# tennisfortwoL151.net
KiCad netlist of a schematic drawn in EAGLE
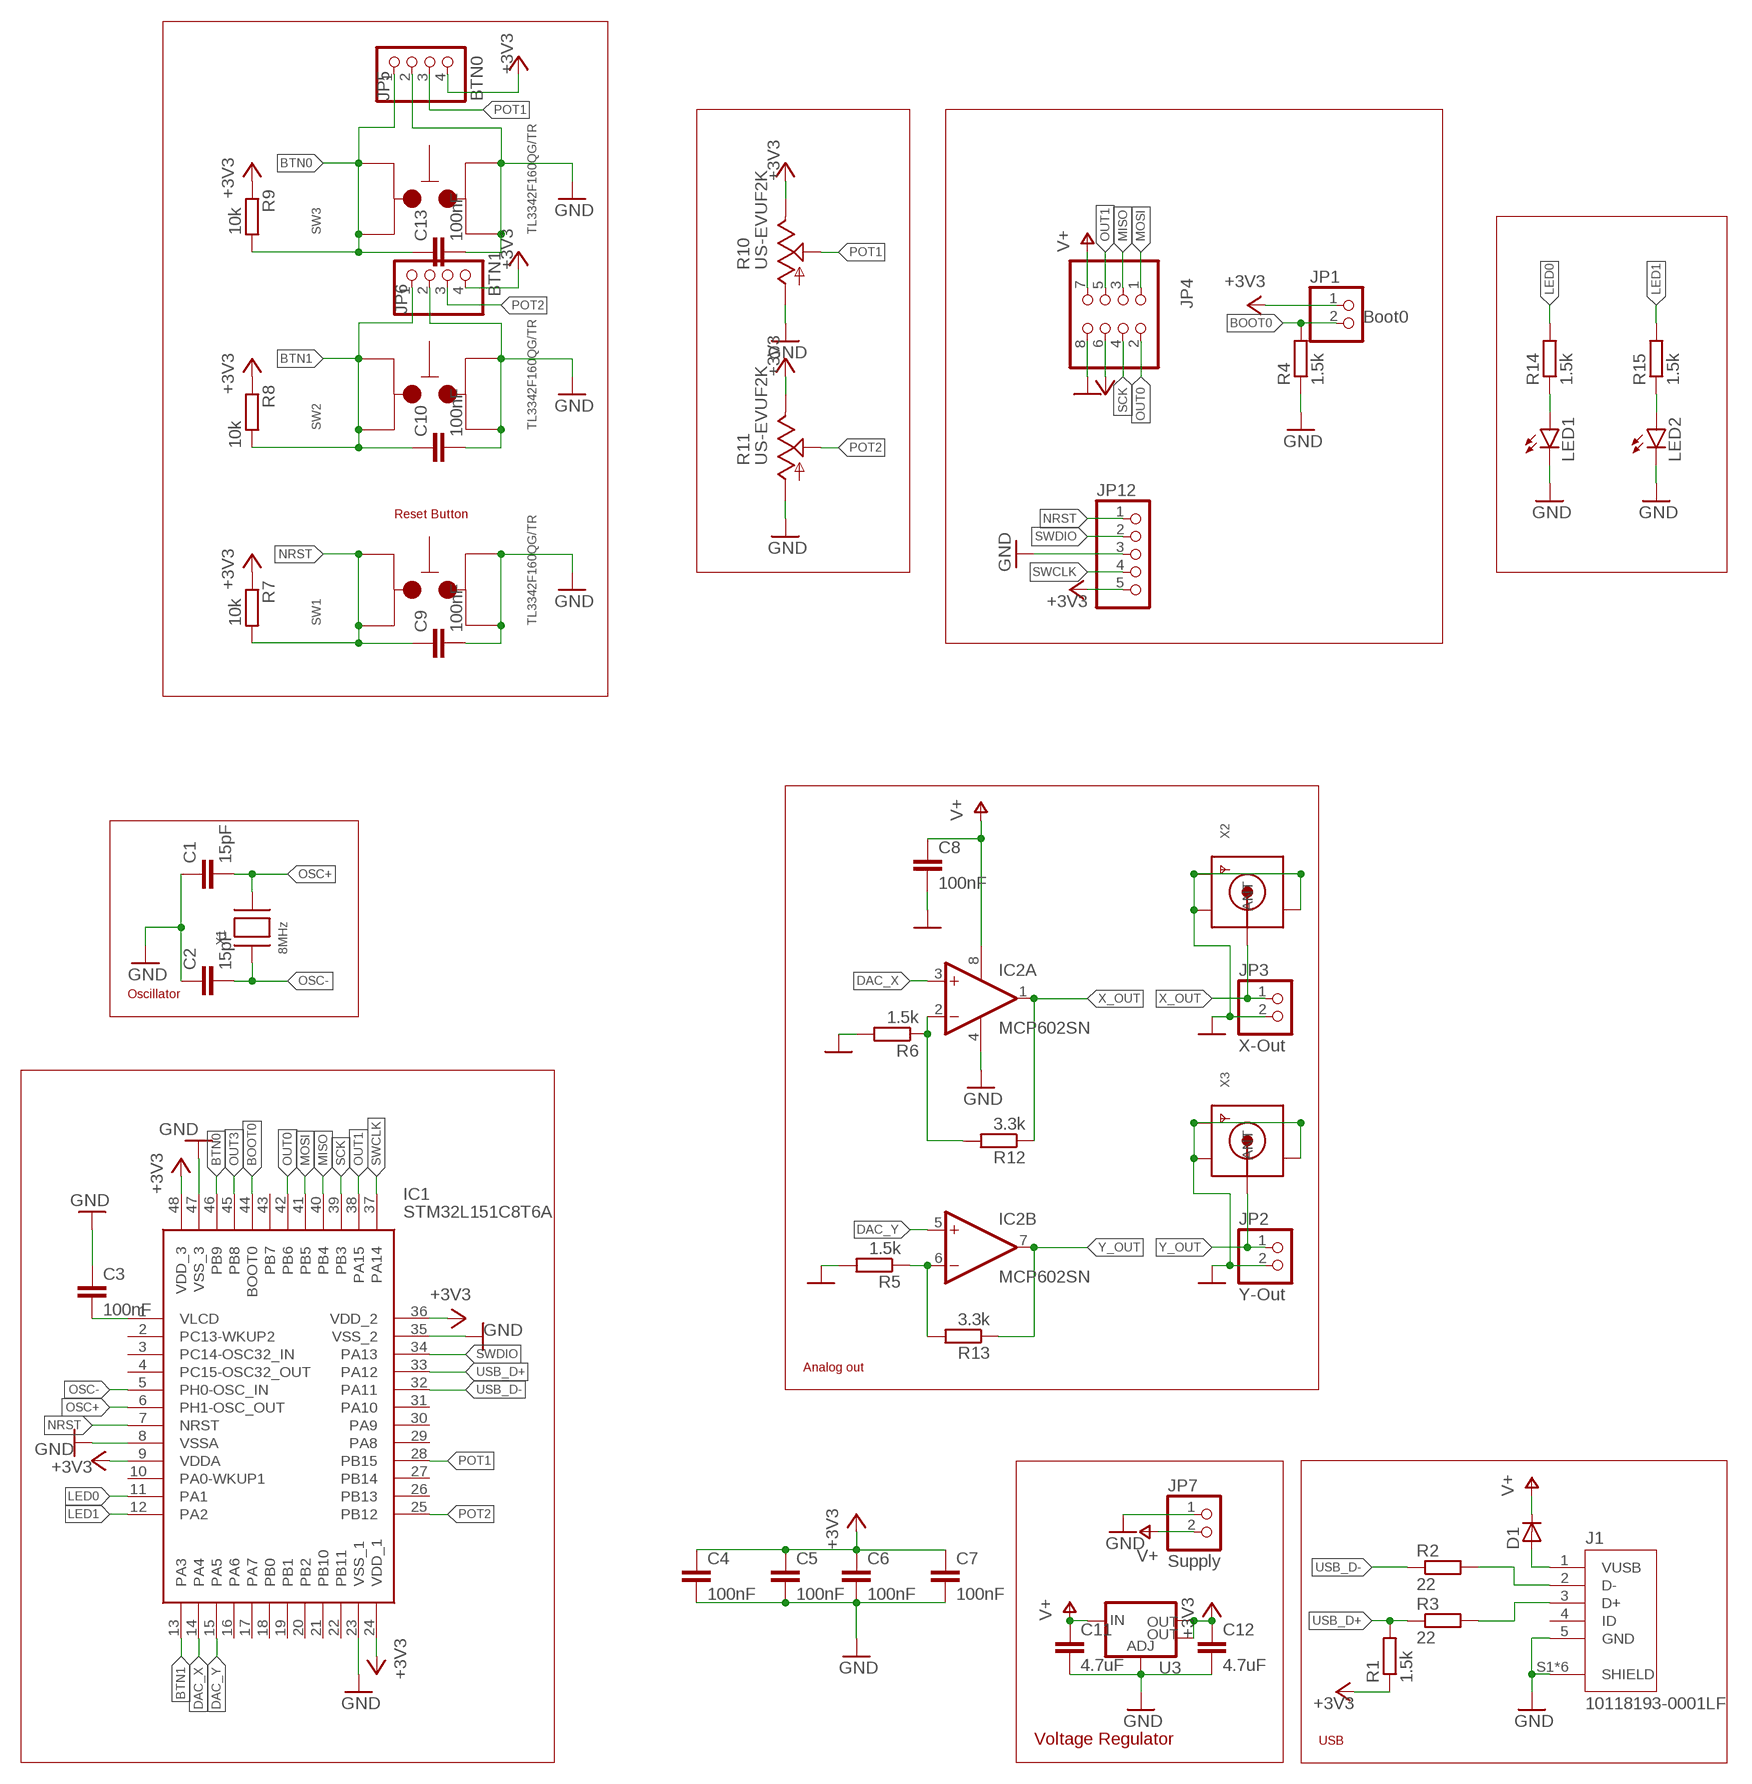
[diagram p0: schematic, sheet 1]

(export (version "E")
  (design (tool "Eeschema 10.0.6"))
  (components
    (comp (ref "C1")
      (value "15pF")
      (footprint "eagle-import:C0603")
      (libsource (lib "eagle-import") (part "C-EUC0603"))
    )
    (comp (ref "C2")
      (value "15pF")
      (footprint "eagle-import:C0603")
      (libsource (lib "eagle-import") (part "C-EUC0603"))
    )
    (comp (ref "C3")
      (value "100nF")
      (footprint "eagle-import:C0603")
      (libsource (lib "eagle-import") (part "C-EUC0603"))
    )
    (comp (ref "C4")
      (value "100nF")
      (footprint "eagle-import:C0603")
      (libsource (lib "eagle-import") (part "C-EUC0603"))
    )
    (comp (ref "C5")
      (value "100nF")
      (footprint "eagle-import:C0603")
      (libsource (lib "eagle-import") (part "C-EUC0603"))
    )
    (comp (ref "C6")
      (value "100nF")
      (footprint "eagle-import:C0603")
      (libsource (lib "eagle-import") (part "C-EUC0603"))
    )
    (comp (ref "C7")
      (value "100nF")
      (footprint "eagle-import:C0603")
      (libsource (lib "eagle-import") (part "C-EUC0603"))
    )
    (comp (ref "C8")
      (value "100nF")
      (footprint "eagle-import:C0603")
      (libsource (lib "eagle-import") (part "C-EUC0603"))
    )
    (comp (ref "C9")
      (value "100nF")
      (footprint "eagle-import:C0603")
      (libsource (lib "eagle-import") (part "C-EUC0603"))
    )
    (comp (ref "C10")
      (value "100nF")
      (footprint "eagle-import:C0603")
      (libsource (lib "eagle-import") (part "C-EUC0603"))
    )
    (comp (ref "C11")
      (value "4.7uF")
      (footprint "eagle-import:C0805")
      (libsource (lib "eagle-import") (part "C-EUC0805"))
    )
    (comp (ref "C12")
      (value "4.7uF")
      (footprint "eagle-import:C0805")
      (libsource (lib "eagle-import") (part "C-EUC0805"))
    )
    (comp (ref "C13")
      (value "100nF")
      (footprint "eagle-import:C0603")
      (libsource (lib "eagle-import") (part "C-EUC0603"))
    )
    (comp (ref "D1")
      (value "DIODESMA")
      (footprint "eagle-import:SMADIODE")
      (libsource (lib "eagle-import") (part "DIODESMA"))
    )
    (comp (ref "IC1")
      (value "STM32L151C8T6A")
      (footprint "eagle-import:QFP50P900X900X160-48N")
      (fields (field (name "MOUSER_PART_NUMBER") "511-STM32L151C8T6A"))
      (libsource (lib "eagle-import") (part "STM32L151C8T6A"))
    )
    (comp (ref "IC2")
      (value "MCP602SN")
      (footprint "eagle-import:SO08")
      (libsource (lib "eagle-import") (part "MCP602SN"))
    )
    (comp (ref "J1")
      (value "10118193-0001LF")
      (footprint "eagle-import:FCI_10118193-0001LF")
      (fields (field (name "MF") "Amphenol ICC"))
      (libsource (lib "eagle-import") (part "10118193-0001LF"))
    )
    (comp (ref "JP1")
      (value "Boot0")
      (footprint "eagle-import:1X02")
      (libsource (lib "eagle-import") (part "PINHD-1X2"))
    )
    (comp (ref "JP2")
      (value "Y-Out")
      (footprint "eagle-import:1X02")
      (libsource (lib "eagle-import") (part "PINHD-1X2"))
    )
    (comp (ref "JP3")
      (value "X-Out")
      (footprint "eagle-import:1X02")
      (libsource (lib "eagle-import") (part "PINHD-1X2"))
    )
    (comp (ref "JP4")
      (value "PINHD-2X4")
      (footprint "eagle-import:2X04")
      (libsource (lib "eagle-import") (part "PINHD-2X4"))
    )
    (comp (ref "JP5")
      (value "BTN0")
      (footprint "eagle-import:1X04_90")
      (libsource (lib "eagle-import") (part "PINHD-1X4/90"))
    )
    (comp (ref "JP6")
      (value "BTN1")
      (footprint "eagle-import:1X04_90")
      (libsource (lib "eagle-import") (part "PINHD-1X4/90"))
    )
    (comp (ref "JP7")
      (value "Supply")
      (footprint "eagle-import:1X02")
      (libsource (lib "eagle-import") (part "PINHD-1X2"))
    )
    (comp (ref "JP12")
      (value "PINHD-1X5")
      (footprint "eagle-import:1X05")
      (libsource (lib "eagle-import") (part "PINHD-1X5"))
    )
    (comp (ref "LED1")
      (value "LEDCHIPLED_0805")
      (footprint "eagle-import:CHIPLED_0805")
      (libsource (lib "eagle-import") (part "LEDCHIPLED_0805"))
    )
    (comp (ref "LED2")
      (value "LEDCHIPLED_0805")
      (footprint "eagle-import:CHIPLED_0805")
      (libsource (lib "eagle-import") (part "LEDCHIPLED_0805"))
    )
    (comp (ref "R1")
      (value "1.5k")
      (footprint "eagle-import:R0603")
      (libsource (lib "eagle-import") (part "R-EU_R0603"))
    )
    (comp (ref "R2")
      (value "22")
      (footprint "eagle-import:R0603")
      (libsource (lib "eagle-import") (part "R-EU_R0603"))
    )
    (comp (ref "R3")
      (value "22")
      (footprint "eagle-import:R0603")
      (libsource (lib "eagle-import") (part "R-EU_R0603"))
    )
    (comp (ref "R4")
      (value "1.5k")
      (footprint "eagle-import:R0603")
      (libsource (lib "eagle-import") (part "R-EU_R0603"))
    )
    (comp (ref "R5")
      (value "1.5k")
      (footprint "eagle-import:R0603")
      (libsource (lib "eagle-import") (part "R-EU_R0603"))
    )
    (comp (ref "R6")
      (value "1.5k")
      (footprint "eagle-import:R0603")
      (libsource (lib "eagle-import") (part "R-EU_R0603"))
    )
    (comp (ref "R7")
      (value "10k")
      (footprint "eagle-import:R0603")
      (libsource (lib "eagle-import") (part "R-EU_R0603"))
    )
    (comp (ref "R8")
      (value "10k")
      (footprint "eagle-import:R0603")
      (libsource (lib "eagle-import") (part "R-EU_R0603"))
    )
    (comp (ref "R9")
      (value "10k")
      (footprint "eagle-import:R0603")
      (libsource (lib "eagle-import") (part "R-EU_R0603"))
    )
    (comp (ref "R10")
      (value "US-EVUF2K")
      (footprint "eagle-import:EVUFXK")
      (libsource (lib "eagle-import") (part "US-EVUF2K"))
    )
    (comp (ref "R11")
      (value "US-EVUF2K")
      (footprint "eagle-import:EVUFXK")
      (libsource (lib "eagle-import") (part "US-EVUF2K"))
    )
    (comp (ref "R12")
      (value "3.3k")
      (footprint "eagle-import:R0603")
      (libsource (lib "eagle-import") (part "R-EU_R0603"))
    )
    (comp (ref "R13")
      (value "3.3k")
      (footprint "eagle-import:R0603")
      (libsource (lib "eagle-import") (part "R-EU_R0603"))
    )
    (comp (ref "R14")
      (value "1.5k")
      (footprint "eagle-import:R0603")
      (libsource (lib "eagle-import") (part "R-EU_R0603"))
    )
    (comp (ref "R15")
      (value "1.5k")
      (footprint "eagle-import:R0603")
      (libsource (lib "eagle-import") (part "R-EU_R0603"))
    )
    (comp (ref "SW1")
      (value "TL3342F160QG/TR")
      (footprint "eagle-import:TL3342F160QG_TR")
      (fields
        (field (name "DIGI_KEY_PART_NUMBER") "EG2531CT-ND")
        (field (name "MANUFACTURER") "E-Switch")
        (field (name "CREATED_BY") "PCBLayout.com")
      )
      (libsource (lib "eagle-import") (part "TL3342F160QG/TR"))
    )
    (comp (ref "SW2")
      (value "TL3342F160QG/TR")
      (footprint "eagle-import:TL3342F160QG_TR")
      (fields
        (field (name "DIGI_KEY_PART_NUMBER") "EG2531CT-ND")
        (field (name "MANUFACTURER") "E-Switch")
        (field (name "CREATED_BY") "PCBLayout.com")
      )
      (libsource (lib "eagle-import") (part "TL3342F160QG/TR"))
    )
    (comp (ref "SW3")
      (value "TL3342F160QG/TR")
      (footprint "eagle-import:TL3342F160QG_TR")
      (fields
        (field (name "DIGI_KEY_PART_NUMBER") "EG2531CT-ND")
        (field (name "MANUFACTURER") "E-Switch")
        (field (name "CREATED_BY") "PCBLayout.com")
      )
      (libsource (lib "eagle-import") (part "TL3342F160QG/TR"))
    )
    (comp (ref "U3")
      (value "V_REG_LM1117SOT223")
      (footprint "eagle-import:SOT223")
      (libsource (lib "eagle-import") (part "V_REG_LM1117SOT223"))
    )
    (comp (ref "X1")
      (value "8MHz")
      (footprint "eagle-import:NX5032")
      (libsource (lib "eagle-import") (part "XTALNX5032"))
    )
    (comp (ref "X2")
      (value "SMACONNECTOR_EDGE")
      (footprint "eagle-import:SMA_EDGELAUNCH")
      (libsource (lib "eagle-import") (part "SMACONNECTOR_EDGE"))
    )
    (comp (ref "X3")
      (value "SMACONNECTOR_EDGE")
      (footprint "eagle-import:SMA_EDGELAUNCH")
      (libsource (lib "eagle-import") (part "SMACONNECTOR_EDGE"))
    )
  )
  (nets
    (net (code "1") (name "+3V3") (class "Default")
      (node (ref "C12") (pin "1") (pinfunction "1_1") (pintype "passive"))
      (node (ref "C4") (pin "1") (pinfunction "1_1") (pintype "passive"))
      (node (ref "C5") (pin "1") (pinfunction "1_1") (pintype "passive"))
      (node (ref "C6") (pin "1") (pinfunction "1_1") (pintype "passive"))
      (node (ref "C7") (pin "1") (pinfunction "1_1") (pintype "passive"))
      (node (ref "IC1") (pin "24") (pinfunction "VDD_1_24") (pintype "bidirectional"))
      (node (ref "IC1") (pin "36") (pinfunction "VDD_2_36") (pintype "bidirectional"))
      (node (ref "IC1") (pin "48") (pinfunction "VDD_3_48") (pintype "bidirectional"))
      (node (ref "IC1") (pin "9") (pinfunction "VDDA_9") (pintype "bidirectional"))
      (node (ref "JP1") (pin "1") (pinfunction "1_1") (pintype "passive"))
      (node (ref "JP12") (pin "5") (pinfunction "5_5") (pintype "passive"))
      (node (ref "JP4") (pin "6") (pinfunction "6_6") (pintype "passive"))
      (node (ref "JP5") (pin "4") (pinfunction "4_4") (pintype "passive"))
      (node (ref "JP6") (pin "4") (pinfunction "4_4") (pintype "passive"))
      (node (ref "R1") (pin "1") (pinfunction "1_1") (pintype "passive"))
      (node (ref "R10") (pin "3") (pinfunction "E_3") (pintype "passive"))
      (node (ref "R11") (pin "3") (pinfunction "E_3") (pintype "passive"))
      (node (ref "R7") (pin "1") (pinfunction "1_1") (pintype "passive"))
      (node (ref "R8") (pin "1") (pinfunction "1_1") (pintype "passive"))
      (node (ref "R9") (pin "1") (pinfunction "1_1") (pintype "passive"))
      (node (ref "U3") (pin "2") (pinfunction "OUT_2") (pintype "output"))
      (node (ref "U3") (pin "4") (pinfunction "OUT_4") (pintype "output"))
    )
    (net (code "2") (name "BOOT0") (class "Default")
      (node (ref "IC1") (pin "44") (pinfunction "BOOT0_44") (pintype "bidirectional"))
      (node (ref "JP1") (pin "2") (pinfunction "2_2") (pintype "passive"))
      (node (ref "R4") (pin "2") (pinfunction "2_2") (pintype "passive"))
    )
    (net (code "3") (name "BTN0") (class "Default")
      (node (ref "C13") (pin "1") (pinfunction "1_1") (pintype "passive"))
      (node (ref "IC1") (pin "46") (pinfunction "PB9_46") (pintype "bidirectional"))
      (node (ref "JP5") (pin "1") (pinfunction "1_1") (pintype "passive"))
      (node (ref "R9") (pin "2") (pinfunction "2_2") (pintype "passive"))
      (node (ref "SW3") (pin "3") (pinfunction "3_3") (pintype "passive"))
      (node (ref "SW3") (pin "4") (pinfunction "4_4") (pintype "passive"))
    )
    (net (code "4") (name "BTN1") (class "Default")
      (node (ref "C10") (pin "1") (pinfunction "1_1") (pintype "passive"))
      (node (ref "IC1") (pin "13") (pinfunction "PA3_13") (pintype "bidirectional"))
      (node (ref "JP6") (pin "1") (pinfunction "1_1") (pintype "passive"))
      (node (ref "R8") (pin "2") (pinfunction "2_2") (pintype "passive"))
      (node (ref "SW2") (pin "3") (pinfunction "3_3") (pintype "passive"))
      (node (ref "SW2") (pin "4") (pinfunction "4_4") (pintype "passive"))
    )
    (net (code "5") (name "DAC_X") (class "Default")
      (node (ref "IC1") (pin "14") (pinfunction "PA4_14") (pintype "bidirectional"))
      (node (ref "IC2") (pin "3") (pinfunction "+IN_3") (pintype "input"))
    )
    (net (code "6") (name "DAC_Y") (class "Default")
      (node (ref "IC1") (pin "15") (pinfunction "PA5_15") (pintype "bidirectional"))
      (node (ref "IC2") (pin "5") (pinfunction "+IN_5") (pintype "input"))
    )
    (net (code "7") (name "GND") (class "Default")
      (node (ref "C1") (pin "1") (pinfunction "1_1") (pintype "passive"))
      (node (ref "C10") (pin "2") (pinfunction "2_2") (pintype "passive"))
      (node (ref "C11") (pin "2") (pinfunction "2_2") (pintype "passive"))
      (node (ref "C12") (pin "2") (pinfunction "2_2") (pintype "passive"))
      (node (ref "C13") (pin "2") (pinfunction "2_2") (pintype "passive"))
      (node (ref "C2") (pin "1") (pinfunction "1_1") (pintype "passive"))
      (node (ref "C3") (pin "1") (pinfunction "1_1") (pintype "passive"))
      (node (ref "C4") (pin "2") (pinfunction "2_2") (pintype "passive"))
      (node (ref "C5") (pin "2") (pinfunction "2_2") (pintype "passive"))
      (node (ref "C6") (pin "2") (pinfunction "2_2") (pintype "passive"))
      (node (ref "C7") (pin "2") (pinfunction "2_2") (pintype "passive"))
      (node (ref "C8") (pin "2") (pinfunction "2_2") (pintype "passive"))
      (node (ref "C9") (pin "2") (pinfunction "2_2") (pintype "passive"))
      (node (ref "IC1") (pin "23") (pinfunction "VSS_1_23") (pintype "bidirectional"))
      (node (ref "IC1") (pin "35") (pinfunction "VSS_2_35") (pintype "bidirectional"))
      (node (ref "IC1") (pin "47") (pinfunction "VSS_3_47") (pintype "bidirectional"))
      (node (ref "IC1") (pin "8") (pinfunction "VSSA_8") (pintype "bidirectional"))
      (node (ref "IC2") (pin "4") (pinfunction "V-_4") (pintype "power_in"))
      (node (ref "J1") (pin "5") (pinfunction "GND_5") (pintype "passive"))
      (node (ref "J1") (pin "S1") (pinfunction "SHIELD_S1") (pintype "passive"))
      (node (ref "J1") (pin "S2") (pinfunction "SHIELD_S2") (pintype "passive"))
      (node (ref "J1") (pin "S3") (pinfunction "SHIELD_S3") (pintype "passive"))
      (node (ref "J1") (pin "S4") (pinfunction "SHIELD_S4") (pintype "passive"))
      (node (ref "J1") (pin "S5") (pinfunction "SHIELD_S5") (pintype "passive"))
      (node (ref "J1") (pin "S6") (pinfunction "SHIELD_S6") (pintype "passive"))
      (node (ref "JP12") (pin "3") (pinfunction "3_3") (pintype "passive"))
      (node (ref "JP2") (pin "2") (pinfunction "2_2") (pintype "passive"))
      (node (ref "JP3") (pin "2") (pinfunction "2_2") (pintype "passive"))
      (node (ref "JP4") (pin "8") (pinfunction "8_8") (pintype "passive"))
      (node (ref "JP5") (pin "2") (pinfunction "2_2") (pintype "passive"))
      (node (ref "JP6") (pin "2") (pinfunction "2_2") (pintype "passive"))
      (node (ref "JP7") (pin "1") (pinfunction "1_1") (pintype "passive"))
      (node (ref "LED1") (pin "C") (pinfunction "C_C") (pintype "passive"))
      (node (ref "LED2") (pin "C") (pinfunction "C_C") (pintype "passive"))
      (node (ref "R10") (pin "1") (pinfunction "A_1") (pintype "passive"))
      (node (ref "R11") (pin "1") (pinfunction "A_1") (pintype "passive"))
      (node (ref "R4") (pin "1") (pinfunction "1_1") (pintype "passive"))
      (node (ref "R5") (pin "2") (pinfunction "2_2") (pintype "passive"))
      (node (ref "R6") (pin "2") (pinfunction "2_2") (pintype "passive"))
      (node (ref "SW1") (pin "1") (pinfunction "1_1") (pintype "passive"))
      (node (ref "SW1") (pin "2") (pinfunction "2_2") (pintype "passive"))
      (node (ref "SW2") (pin "1") (pinfunction "1_1") (pintype "passive"))
      (node (ref "SW2") (pin "2") (pinfunction "2_2") (pintype "passive"))
      (node (ref "SW3") (pin "1") (pinfunction "1_1") (pintype "passive"))
      (node (ref "SW3") (pin "2") (pinfunction "2_2") (pintype "passive"))
      (node (ref "U3") (pin "1") (pinfunction "ADJ_1") (pintype "input"))
      (node (ref "X2") (pin "GND@1") (pinfunction "GND4_GND@1") (pintype "power_in"))
      (node (ref "X2") (pin "GND@2") (pinfunction "GND3_GND@2") (pintype "power_in"))
      (node (ref "X2") (pin "GND@3") (pinfunction "GND2_GND@3") (pintype "power_in"))
      (node (ref "X2") (pin "GND@4") (pinfunction "GND1_GND@4") (pintype "power_in"))
      (node (ref "X3") (pin "GND@1") (pinfunction "GND4_GND@1") (pintype "power_in"))
      (node (ref "X3") (pin "GND@2") (pinfunction "GND3_GND@2") (pintype "power_in"))
      (node (ref "X3") (pin "GND@3") (pinfunction "GND2_GND@3") (pintype "power_in"))
      (node (ref "X3") (pin "GND@4") (pinfunction "GND1_GND@4") (pintype "power_in"))
    )
    (net (code "8") (name "LED0") (class "Default")
      (node (ref "IC1") (pin "11") (pinfunction "PA1_11") (pintype "bidirectional"))
      (node (ref "R14") (pin "2") (pinfunction "2_2") (pintype "passive"))
    )
    (net (code "9") (name "LED1") (class "Default")
      (node (ref "IC1") (pin "12") (pinfunction "PA2_12") (pintype "bidirectional"))
      (node (ref "R15") (pin "2") (pinfunction "2_2") (pintype "passive"))
    )
    (net (code "10") (name "MISO") (class "Default")
      (node (ref "IC1") (pin "40") (pinfunction "PB4_40") (pintype "bidirectional"))
      (node (ref "JP4") (pin "3") (pinfunction "3_3") (pintype "passive"))
    )
    (net (code "11") (name "MOSI") (class "Default")
      (node (ref "IC1") (pin "41") (pinfunction "PB5_41") (pintype "bidirectional"))
      (node (ref "JP4") (pin "1") (pinfunction "1_1") (pintype "passive"))
    )
    (net (code "12") (name "NRST") (class "Default")
      (node (ref "C9") (pin "1") (pinfunction "1_1") (pintype "passive"))
      (node (ref "IC1") (pin "7") (pinfunction "NRST_7") (pintype "bidirectional"))
      (node (ref "JP12") (pin "1") (pinfunction "1_1") (pintype "passive"))
      (node (ref "R7") (pin "2") (pinfunction "2_2") (pintype "passive"))
      (node (ref "SW1") (pin "3") (pinfunction "3_3") (pintype "passive"))
      (node (ref "SW1") (pin "4") (pinfunction "4_4") (pintype "passive"))
    )
    (net (code "13") (name "Net-(IC1-VLCD)") (class "Default")
      (node (ref "C3") (pin "2") (pinfunction "2_2") (pintype "passive"))
      (node (ref "IC1") (pin "1") (pinfunction "VLCD_1") (pintype "bidirectional"))
    )
    (net (code "14") (name "Net-(IC2A--IN)") (class "Default")
      (node (ref "IC2") (pin "2") (pinfunction "-IN_2") (pintype "input"))
      (node (ref "R12") (pin "2") (pinfunction "2_2") (pintype "passive"))
      (node (ref "R6") (pin "1") (pinfunction "1_1") (pintype "passive"))
    )
    (net (code "15") (name "Net-(IC2B--IN)") (class "Default")
      (node (ref "IC2") (pin "6") (pinfunction "-IN_6") (pintype "input"))
      (node (ref "R13") (pin "2") (pinfunction "2_2") (pintype "passive"))
      (node (ref "R5") (pin "1") (pinfunction "1_1") (pintype "passive"))
    )
    (net (code "16") (name "Net-(J1-D+)") (class "Default")
      (node (ref "J1") (pin "3") (pinfunction "D+_3") (pintype "passive"))
      (node (ref "R3") (pin "2") (pinfunction "2_2") (pintype "passive"))
    )
    (net (code "17") (name "Net-(J1-D-)") (class "Default")
      (node (ref "J1") (pin "2") (pinfunction "D-_2") (pintype "passive"))
      (node (ref "R2") (pin "2") (pinfunction "2_2") (pintype "passive"))
    )
    (net (code "18") (name "Net-(J1-VUSB)") (class "Default")
      (node (ref "D1") (pin "A") (pinfunction "A_A") (pintype "passive"))
      (node (ref "J1") (pin "1") (pinfunction "VUSB_1") (pintype "passive"))
    )
    (net (code "19") (name "Net-(LED1-PadA)") (class "Default")
      (node (ref "LED1") (pin "A") (pinfunction "A_A") (pintype "passive"))
      (node (ref "R14") (pin "1") (pinfunction "1_1") (pintype "passive"))
    )
    (net (code "20") (name "Net-(LED2-PadA)") (class "Default")
      (node (ref "LED2") (pin "A") (pinfunction "A_A") (pintype "passive"))
      (node (ref "R15") (pin "1") (pinfunction "1_1") (pintype "passive"))
    )
    (net (code "21") (name "OSC+") (class "Default")
      (node (ref "C1") (pin "2") (pinfunction "2_2") (pintype "passive"))
      (node (ref "IC1") (pin "6") (pinfunction "PH1-OSC_OUT_6") (pintype "bidirectional"))
      (node (ref "X1") (pin "P$2") (pinfunction "P$2_P$2") (pintype "bidirectional"))
    )
    (net (code "22") (name "OSC-") (class "Default")
      (node (ref "C2") (pin "2") (pinfunction "2_2") (pintype "passive"))
      (node (ref "IC1") (pin "5") (pinfunction "PH0-OSC_IN_5") (pintype "bidirectional"))
      (node (ref "X1") (pin "P$1") (pinfunction "P$1_P$1") (pintype "bidirectional"))
    )
    (net (code "23") (name "OUT0") (class "Default")
      (node (ref "IC1") (pin "42") (pinfunction "PB6_42") (pintype "bidirectional"))
      (node (ref "JP4") (pin "2") (pinfunction "2_2") (pintype "passive"))
    )
    (net (code "24") (name "OUT1") (class "Default")
      (node (ref "IC1") (pin "38") (pinfunction "PA15_38") (pintype "bidirectional"))
      (node (ref "JP4") (pin "5") (pinfunction "5_5") (pintype "passive"))
    )
    (net (code "25") (name "OUT3") (class "Default")
      (node (ref "IC1") (pin "45") (pinfunction "PB8_45") (pintype "bidirectional"))
    )
    (net (code "26") (name "POT1") (class "Default")
      (node (ref "IC1") (pin "28") (pinfunction "PB15_28") (pintype "bidirectional"))
      (node (ref "JP5") (pin "3") (pinfunction "3_3") (pintype "passive"))
      (node (ref "R10") (pin "2") (pinfunction "S_2") (pintype "passive"))
    )
    (net (code "27") (name "POT2") (class "Default")
      (node (ref "IC1") (pin "25") (pinfunction "PB12_25") (pintype "bidirectional"))
      (node (ref "JP6") (pin "3") (pinfunction "3_3") (pintype "passive"))
      (node (ref "R11") (pin "2") (pinfunction "S_2") (pintype "passive"))
    )
    (net (code "28") (name "SCK") (class "Default")
      (node (ref "IC1") (pin "39") (pinfunction "PB3_39") (pintype "bidirectional"))
      (node (ref "JP4") (pin "4") (pinfunction "4_4") (pintype "passive"))
    )
    (net (code "29") (name "SWCLK") (class "Default")
      (node (ref "IC1") (pin "37") (pinfunction "PA14_37") (pintype "bidirectional"))
      (node (ref "JP12") (pin "4") (pinfunction "4_4") (pintype "passive"))
    )
    (net (code "30") (name "SWDIO") (class "Default")
      (node (ref "IC1") (pin "34") (pinfunction "PA13_34") (pintype "bidirectional"))
      (node (ref "JP12") (pin "2") (pinfunction "2_2") (pintype "passive"))
    )
    (net (code "31") (name "USB_D+") (class "Default")
      (node (ref "IC1") (pin "33") (pinfunction "PA12_33") (pintype "bidirectional"))
      (node (ref "R1") (pin "2") (pinfunction "2_2") (pintype "passive"))
      (node (ref "R3") (pin "1") (pinfunction "1_1") (pintype "passive"))
    )
    (net (code "32") (name "USB_D-") (class "Default")
      (node (ref "IC1") (pin "32") (pinfunction "PA11_32") (pintype "bidirectional"))
      (node (ref "R2") (pin "1") (pinfunction "1_1") (pintype "passive"))
    )
    (net (code "33") (name "V+") (class "Default")
      (node (ref "C11") (pin "1") (pinfunction "1_1") (pintype "passive"))
      (node (ref "C8") (pin "1") (pinfunction "1_1") (pintype "passive"))
      (node (ref "D1") (pin "C") (pinfunction "C_C") (pintype "passive"))
      (node (ref "IC2") (pin "8") (pinfunction "V+_8") (pintype "power_in"))
      (node (ref "JP4") (pin "7") (pinfunction "7_7") (pintype "passive"))
      (node (ref "JP7") (pin "2") (pinfunction "2_2") (pintype "passive"))
      (node (ref "U3") (pin "3") (pinfunction "IN_3") (pintype "input"))
    )
    (net (code "34") (name "X_OUT") (class "Default")
      (node (ref "IC2") (pin "1") (pinfunction "OUT_1") (pintype "output"))
      (node (ref "JP3") (pin "1") (pinfunction "1_1") (pintype "passive"))
      (node (ref "R12") (pin "1") (pinfunction "1_1") (pintype "passive"))
      (node (ref "X2") (pin "P") (pinfunction "ANT_P") (pintype "bidirectional"))
    )
    (net (code "35") (name "Y_OUT") (class "Default")
      (node (ref "IC2") (pin "7") (pinfunction "OUT_7") (pintype "output"))
      (node (ref "JP2") (pin "1") (pinfunction "1_1") (pintype "passive"))
      (node (ref "R13") (pin "1") (pinfunction "1_1") (pintype "passive"))
      (node (ref "X3") (pin "P") (pinfunction "ANT_P") (pintype "bidirectional"))
    )
    (net (code "36") (name "unconnected-(IC1-PA0-WKUP1-Pad10)") (class "Default")
      (node (ref "IC1") (pin "10") (pinfunction "PA0-WKUP1_10") (pintype "bidirectional"))
    )
    (net (code "37") (name "unconnected-(IC1-PA6-Pad16)") (class "Default")
      (node (ref "IC1") (pin "16") (pinfunction "PA6_16") (pintype "bidirectional"))
    )
    (net (code "38") (name "unconnected-(IC1-PA7-Pad17)") (class "Default")
      (node (ref "IC1") (pin "17") (pinfunction "PA7_17") (pintype "bidirectional"))
    )
    (net (code "39") (name "unconnected-(IC1-PA8-Pad29)") (class "Default")
      (node (ref "IC1") (pin "29") (pinfunction "PA8_29") (pintype "bidirectional"))
    )
    (net (code "40") (name "unconnected-(IC1-PA9-Pad30)") (class "Default")
      (node (ref "IC1") (pin "30") (pinfunction "PA9_30") (pintype "bidirectional"))
    )
    (net (code "41") (name "unconnected-(IC1-PA10-Pad31)") (class "Default")
      (node (ref "IC1") (pin "31") (pinfunction "PA10_31") (pintype "bidirectional"))
    )
    (net (code "42") (name "unconnected-(IC1-PB0-Pad18)") (class "Default")
      (node (ref "IC1") (pin "18") (pinfunction "PB0_18") (pintype "bidirectional"))
    )
    (net (code "43") (name "unconnected-(IC1-PB1-Pad19)") (class "Default")
      (node (ref "IC1") (pin "19") (pinfunction "PB1_19") (pintype "bidirectional"))
    )
    (net (code "44") (name "unconnected-(IC1-PB2-Pad20)") (class "Default")
      (node (ref "IC1") (pin "20") (pinfunction "PB2_20") (pintype "bidirectional"))
    )
    (net (code "45") (name "unconnected-(IC1-PB7-Pad43)") (class "Default")
      (node (ref "IC1") (pin "43") (pinfunction "PB7_43") (pintype "bidirectional"))
    )
    (net (code "46") (name "unconnected-(IC1-PB10-Pad21)") (class "Default")
      (node (ref "IC1") (pin "21") (pinfunction "PB10_21") (pintype "bidirectional"))
    )
    (net (code "47") (name "unconnected-(IC1-PB11-Pad22)") (class "Default")
      (node (ref "IC1") (pin "22") (pinfunction "PB11_22") (pintype "bidirectional"))
    )
    (net (code "48") (name "unconnected-(IC1-PB13-Pad26)") (class "Default")
      (node (ref "IC1") (pin "26") (pinfunction "PB13_26") (pintype "bidirectional"))
    )
    (net (code "49") (name "unconnected-(IC1-PB14-Pad27)") (class "Default")
      (node (ref "IC1") (pin "27") (pinfunction "PB14_27") (pintype "bidirectional"))
    )
    (net (code "50") (name "unconnected-(IC1-PC13-WKUP2-Pad2)") (class "Default")
      (node (ref "IC1") (pin "2") (pinfunction "PC13-WKUP2_2") (pintype "bidirectional"))
    )
    (net (code "51") (name "unconnected-(IC1-PC14-OSC32_IN-Pad3)") (class "Default")
      (node (ref "IC1") (pin "3") (pinfunction "PC14-OSC32_IN_3") (pintype "bidirectional"))
    )
    (net (code "52") (name "unconnected-(IC1-PC15-OSC32_OUT-Pad4)") (class "Default")
      (node (ref "IC1") (pin "4") (pinfunction "PC15-OSC32_OUT_4") (pintype "bidirectional"))
    )
    (net (code "53") (name "unconnected-(J1-ID-Pad4)") (class "Default")
      (node (ref "J1") (pin "4") (pinfunction "ID_4") (pintype "passive"))
    )
  )
)
